# v00_hardware_hole.net
KiCad netlist of a schematic drawn in EAGLE
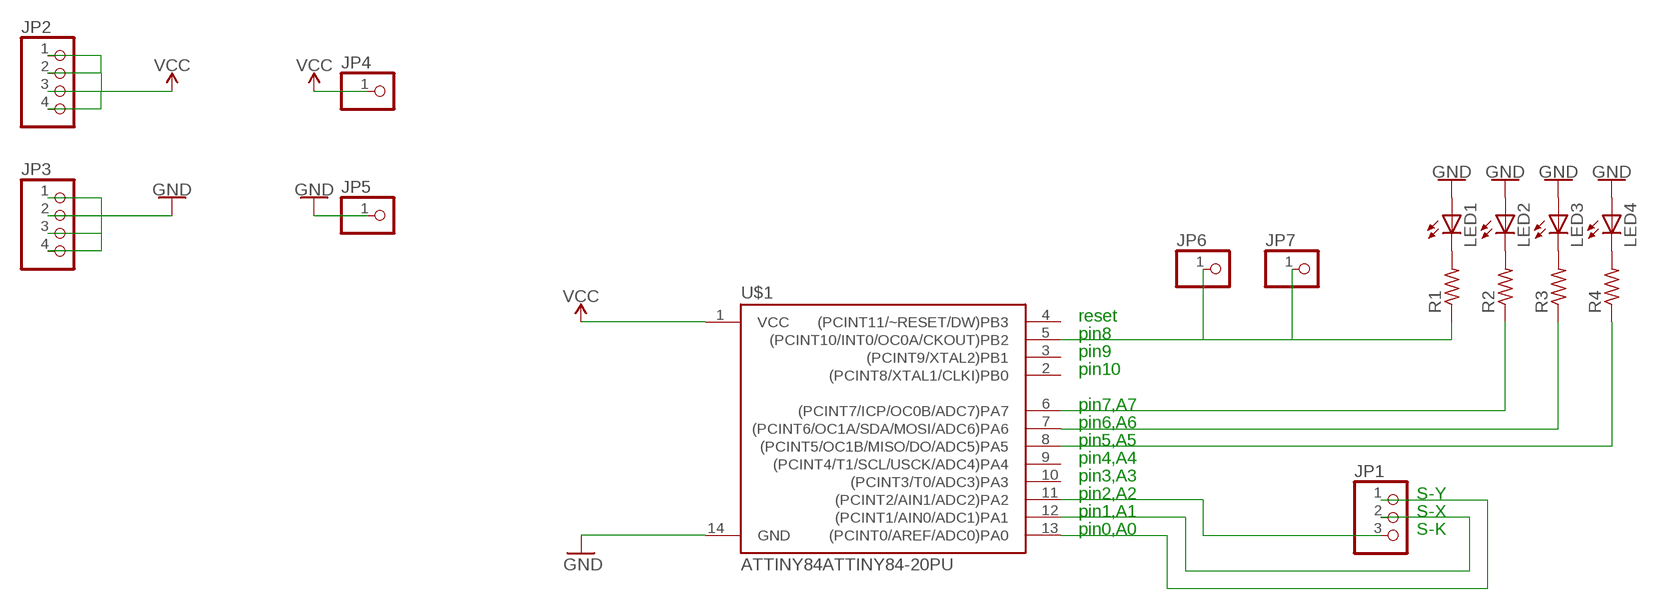
[diagram p0: schematic, sheet 1]

(export (version "E")
  (design (tool "Eeschema 10.0.6"))
  (components
    (comp (ref "JP1")
      (value "PINHD-1X3")
      (footprint "eagle-import:1X03")
      (libsource (lib "eagle-import") (part "PINHD-1X3"))
    )
    (comp (ref "JP2")
      (value "PINHD-1X4")
      (footprint "eagle-import:1X04")
      (libsource (lib "eagle-import") (part "PINHD-1X4"))
    )
    (comp (ref "JP3")
      (value "PINHD-1X4")
      (footprint "eagle-import:1X04")
      (libsource (lib "eagle-import") (part "PINHD-1X4"))
    )
    (comp (ref "JP4")
      (value "PINHD-1X1")
      (footprint "eagle-import:1X01")
      (libsource (lib "eagle-import") (part "PINHD-1X1"))
    )
    (comp (ref "JP5")
      (value "PINHD-1X1")
      (footprint "eagle-import:1X01")
      (libsource (lib "eagle-import") (part "PINHD-1X1"))
    )
    (comp (ref "JP6")
      (value "PINHD-1X1")
      (footprint "eagle-import:1X01")
      (libsource (lib "eagle-import") (part "PINHD-1X1"))
    )
    (comp (ref "JP7")
      (value "PINHD-1X1")
      (footprint "eagle-import:1X01")
      (libsource (lib "eagle-import") (part "PINHD-1X1"))
    )
    (comp (ref "LED1")
      (value "LED5MM")
      (footprint "eagle-import:LED5MM")
      (libsource (lib "eagle-import") (part "LED5MM"))
    )
    (comp (ref "LED2")
      (value "LED5MM")
      (footprint "eagle-import:LED5MM")
      (libsource (lib "eagle-import") (part "LED5MM"))
    )
    (comp (ref "LED3")
      (value "LED5MM")
      (footprint "eagle-import:LED5MM")
      (libsource (lib "eagle-import") (part "LED5MM"))
    )
    (comp (ref "LED4")
      (value "LED5MM")
      (footprint "eagle-import:LED5MM")
      (libsource (lib "eagle-import") (part "LED5MM"))
    )
    (comp (ref "R1")
      (value "R-US_0204/7")
      (footprint "eagle-import:0204_7")
      (libsource (lib "eagle-import") (part "R-US_0204/7"))
    )
    (comp (ref "R2")
      (value "R-US_0204/7")
      (footprint "eagle-import:0204_7")
      (libsource (lib "eagle-import") (part "R-US_0204/7"))
    )
    (comp (ref "R3")
      (value "R-US_0204/7")
      (footprint "eagle-import:0204_7")
      (libsource (lib "eagle-import") (part "R-US_0204/7"))
    )
    (comp (ref "R4")
      (value "R-US_0204/7")
      (footprint "eagle-import:0204_7")
      (libsource (lib "eagle-import") (part "R-US_0204/7"))
    )
    (comp (ref "U$1")
      (value "ATTINY84ATTINY84-20PU")
      (footprint "eagle-import:DIP14")
      (libsource (lib "eagle-import") (part "ATTINY84ATTINY84-20PU"))
    )
  )
  (nets
    (net (code "1") (name "GND") (class "Default")
      (node (ref "JP3") (pin "1") (pinfunction "1_1") (pintype "passive"))
      (node (ref "JP3") (pin "2") (pinfunction "2_2") (pintype "passive"))
      (node (ref "JP3") (pin "3") (pinfunction "3_3") (pintype "passive"))
      (node (ref "JP3") (pin "4") (pinfunction "4_4") (pintype "passive"))
      (node (ref "JP5") (pin "1") (pinfunction "1_1") (pintype "passive"))
      (node (ref "LED1") (pin "A") (pinfunction "A_A") (pintype "passive"))
      (node (ref "LED2") (pin "A") (pinfunction "A_A") (pintype "passive"))
      (node (ref "LED3") (pin "A") (pinfunction "A_A") (pintype "passive"))
      (node (ref "LED4") (pin "A") (pinfunction "A_A") (pintype "passive"))
      (node (ref "U$1") (pin "14") (pinfunction "GND_14") (pintype "bidirectional"))
    )
    (net (code "2") (name "Net-(LED1-C)") (class "Default")
      (node (ref "LED1") (pin "K") (pinfunction "C_K") (pintype "passive"))
      (node (ref "R1") (pin "2") (pinfunction "2_2") (pintype "passive"))
    )
    (net (code "3") (name "Net-(LED2-C)") (class "Default")
      (node (ref "LED2") (pin "K") (pinfunction "C_K") (pintype "passive"))
      (node (ref "R2") (pin "2") (pinfunction "2_2") (pintype "passive"))
    )
    (net (code "4") (name "Net-(LED3-C)") (class "Default")
      (node (ref "LED3") (pin "K") (pinfunction "C_K") (pintype "passive"))
      (node (ref "R3") (pin "2") (pinfunction "2_2") (pintype "passive"))
    )
    (net (code "5") (name "Net-(LED4-C)") (class "Default")
      (node (ref "LED4") (pin "K") (pinfunction "C_K") (pintype "passive"))
      (node (ref "R4") (pin "2") (pinfunction "2_2") (pintype "passive"))
    )
    (net (code "6") (name "Net-(U$1-(PCINT0{slash}AREF{slash}ADC0)PA0)") (class "Default")
      (node (ref "JP1") (pin "1") (pinfunction "1_1") (pintype "passive"))
      (node (ref "U$1") (pin "13") (pinfunction "(PCINT0/AREF/ADC0)PA0_13") (pintype "bidirectional"))
    )
    (net (code "7") (name "Net-(U$1-(PCINT1{slash}AIN0{slash}ADC1)PA1)") (class "Default")
      (node (ref "JP1") (pin "2") (pinfunction "2_2") (pintype "passive"))
      (node (ref "U$1") (pin "12") (pinfunction "(PCINT1/AIN0/ADC1)PA1_12") (pintype "bidirectional"))
    )
    (net (code "8") (name "Net-(U$1-(PCINT2{slash}AIN1{slash}ADC2)PA2)") (class "Default")
      (node (ref "JP1") (pin "3") (pinfunction "3_3") (pintype "passive"))
      (node (ref "U$1") (pin "11") (pinfunction "(PCINT2/AIN1/ADC2)PA2_11") (pintype "bidirectional"))
    )
    (net (code "9") (name "Net-(U$1-(PCINT5{slash}OC1B{slash}MISO{slash}DO{slash}ADC5)PA5)") (class "Default")
      (node (ref "R4") (pin "1") (pinfunction "1_1") (pintype "passive"))
      (node (ref "U$1") (pin "8") (pinfunction "(PCINT5/OC1B/MISO/DO/ADC5)PA5_8") (pintype "bidirectional"))
    )
    (net (code "10") (name "Net-(U$1-(PCINT6{slash}OC1A{slash}SDA{slash}MOSI{slash}ADC6)PA6)") (class "Default")
      (node (ref "R3") (pin "1") (pinfunction "1_1") (pintype "passive"))
      (node (ref "U$1") (pin "7") (pinfunction "(PCINT6/OC1A/SDA/MOSI/ADC6)PA6_7") (pintype "bidirectional"))
    )
    (net (code "11") (name "Net-(U$1-(PCINT7{slash}ICP{slash}OC0B{slash}ADC7)PA7)") (class "Default")
      (node (ref "R2") (pin "1") (pinfunction "1_1") (pintype "passive"))
      (node (ref "U$1") (pin "6") (pinfunction "(PCINT7/ICP/OC0B/ADC7)PA7_6") (pintype "bidirectional"))
    )
    (net (code "12") (name "Net-(U$1-(PCINT10{slash}INT0{slash}OC0A{slash}CKOUT)PB2)") (class "Default")
      (node (ref "JP6") (pin "1") (pinfunction "1_1") (pintype "passive"))
      (node (ref "JP7") (pin "1") (pinfunction "1_1") (pintype "passive"))
      (node (ref "R1") (pin "1") (pinfunction "1_1") (pintype "passive"))
      (node (ref "U$1") (pin "5") (pinfunction "(PCINT10/INT0/OC0A/CKOUT)PB2_5") (pintype "bidirectional"))
    )
    (net (code "13") (name "VCC") (class "Default")
      (node (ref "JP2") (pin "1") (pinfunction "1_1") (pintype "passive"))
      (node (ref "JP2") (pin "2") (pinfunction "2_2") (pintype "passive"))
      (node (ref "JP2") (pin "3") (pinfunction "3_3") (pintype "passive"))
      (node (ref "JP2") (pin "4") (pinfunction "4_4") (pintype "passive"))
      (node (ref "JP4") (pin "1") (pinfunction "1_1") (pintype "passive"))
      (node (ref "U$1") (pin "1") (pinfunction "VCC_1") (pintype "bidirectional"))
    )
    (net (code "14") (name "unconnected-(U$1-(PCINT3{slash}T0{slash}ADC3)PA3-Pad10)") (class "Default")
      (node (ref "U$1") (pin "10") (pinfunction "(PCINT3/T0/ADC3)PA3_10") (pintype "bidirectional"))
    )
    (net (code "15") (name "unconnected-(U$1-(PCINT4{slash}T1{slash}SCL{slash}USCK{slash}ADC4)PA4-Pad9)") (class "Default")
      (node (ref "U$1") (pin "9") (pinfunction "(PCINT4/T1/SCL/USCK/ADC4)PA4_9") (pintype "bidirectional"))
    )
    (net (code "16") (name "unconnected-(U$1-(PCINT8{slash}XTAL1{slash}CLKI)PB0-Pad2)") (class "Default")
      (node (ref "U$1") (pin "2") (pinfunction "(PCINT8/XTAL1/CLKI)PB0_2") (pintype "bidirectional"))
    )
    (net (code "17") (name "unconnected-(U$1-(PCINT9{slash}XTAL2)PB1-Pad3)") (class "Default")
      (node (ref "U$1") (pin "3") (pinfunction "(PCINT9/XTAL2)PB1_3") (pintype "bidirectional"))
    )
    (net (code "18") (name "unconnected-(U$1-(PCINT11{slash}~{RESET{slash}DW})PB3-Pad4)") (class "Default")
      (node (ref "U$1") (pin "4") (pinfunction "(PCINT11/~{RESET/DW})PB3_4") (pintype "bidirectional"))
    )
  )
)
